# nrf52withamp.net
KiCad netlist of a schematic drawn in EAGLE
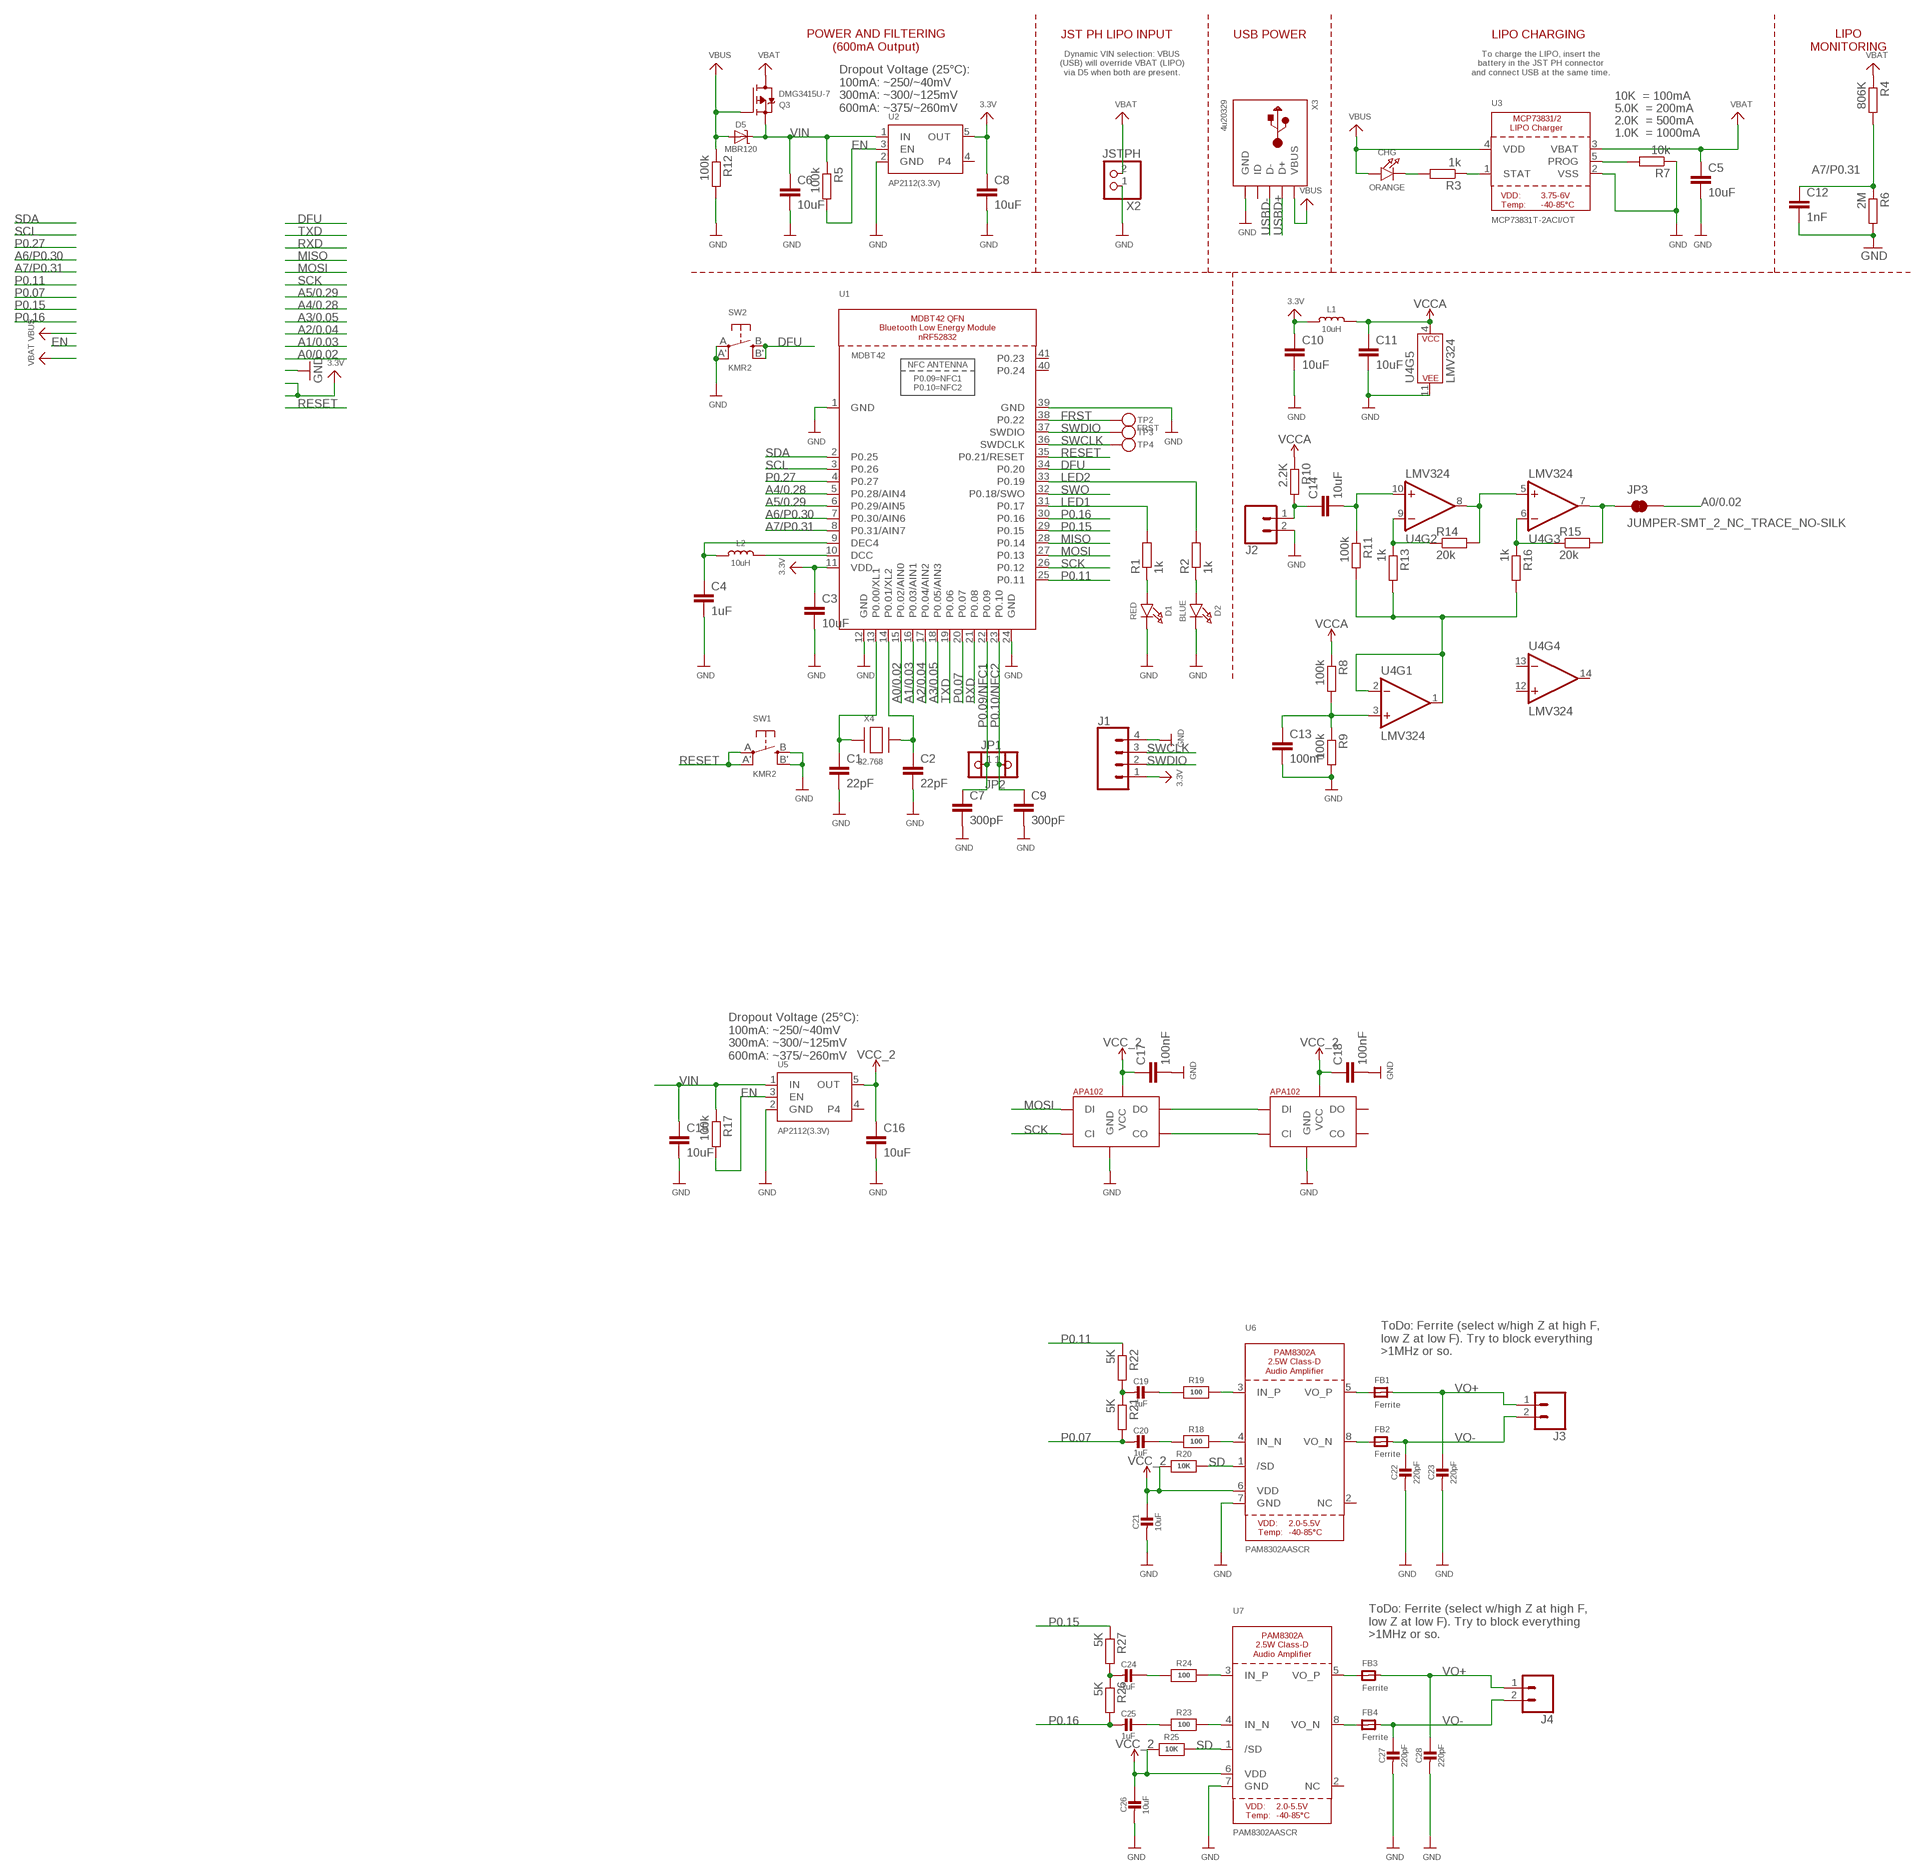
[diagram p0: schematic, sheet 1]

(export (version "E")
  (design (tool "Eeschema 10.0.6"))
  (components
    (comp (ref "C1")
      (value "22pF")
      (footprint "eagle-import:C0805")
      (libsource (lib "eagle-import") (part "C-EUC0805"))
    )
    (comp (ref "C2")
      (value "22pF")
      (footprint "eagle-import:C0805")
      (libsource (lib "eagle-import") (part "C-EUC0805"))
    )
    (comp (ref "C3")
      (value "10uF")
      (footprint "eagle-import:C0805")
      (libsource (lib "eagle-import") (part "C-EUC0805"))
    )
    (comp (ref "C4")
      (value "1uF")
      (footprint "eagle-import:C0805")
      (libsource (lib "eagle-import") (part "C-EUC0805"))
    )
    (comp (ref "C5")
      (value "10uF")
      (footprint "eagle-import:C0805")
      (libsource (lib "eagle-import") (part "C-EUC0805"))
    )
    (comp (ref "C6")
      (value "10uF")
      (footprint "eagle-import:C0805")
      (libsource (lib "eagle-import") (part "C-EUC0805"))
    )
    (comp (ref "C7")
      (value "300pF")
      (footprint "eagle-import:C0805")
      (libsource (lib "eagle-import") (part "C-EUC0805"))
    )
    (comp (ref "C8")
      (value "10uF")
      (footprint "eagle-import:C0805")
      (libsource (lib "eagle-import") (part "C-EUC0805"))
    )
    (comp (ref "C9")
      (value "300pF")
      (footprint "eagle-import:C0805")
      (libsource (lib "eagle-import") (part "C-EUC0805"))
    )
    (comp (ref "C10")
      (value "10uF")
      (footprint "eagle-import:C0805")
      (libsource (lib "eagle-import") (part "C-EUC0805"))
    )
    (comp (ref "C11")
      (value "10uF")
      (footprint "eagle-import:C0805")
      (libsource (lib "eagle-import") (part "C-EUC0805"))
    )
    (comp (ref "C12")
      (value "1nF")
      (footprint "eagle-import:C0805")
      (libsource (lib "eagle-import") (part "C-EUC0805"))
    )
    (comp (ref "C13")
      (value "100nF")
      (footprint "eagle-import:C0805")
      (libsource (lib "eagle-import") (part "C-EUC0805"))
    )
    (comp (ref "C14")
      (value "10uF")
      (footprint "eagle-import:C0805")
      (libsource (lib "eagle-import") (part "C-EUC0805"))
    )
    (comp (ref "C15")
      (value "10uF")
      (footprint "eagle-import:C0805")
      (libsource (lib "eagle-import") (part "C-EUC0805"))
    )
    (comp (ref "C16")
      (value "10uF")
      (footprint "eagle-import:C0805")
      (libsource (lib "eagle-import") (part "C-EUC0805"))
    )
    (comp (ref "C17")
      (value "100nF")
      (footprint "eagle-import:C0805")
      (libsource (lib "eagle-import") (part "C-EUC0805"))
    )
    (comp (ref "C18")
      (value "100nF")
      (footprint "eagle-import:C0805")
      (libsource (lib "eagle-import") (part "C-EUC0805"))
    )
    (comp (ref "C19")
      (value "1uF")
      (footprint "eagle-import:0805-NO")
      (libsource (lib "eagle-import") (part "CAP_CERAMIC0805-NOOUTLINE"))
    )
    (comp (ref "C20")
      (value "1uF")
      (footprint "eagle-import:0805-NO")
      (libsource (lib "eagle-import") (part "CAP_CERAMIC0805-NOOUTLINE"))
    )
    (comp (ref "C21")
      (value "10uF")
      (footprint "eagle-import:0805-NO")
      (libsource (lib "eagle-import") (part "CAP_CERAMIC0805-NOOUTLINE"))
    )
    (comp (ref "C22")
      (value "220pF")
      (footprint "eagle-import:0805-NO")
      (libsource (lib "eagle-import") (part "CAP_CERAMIC0805-NOOUTLINE"))
    )
    (comp (ref "C23")
      (value "220pF")
      (footprint "eagle-import:0805-NO")
      (libsource (lib "eagle-import") (part "CAP_CERAMIC0805-NOOUTLINE"))
    )
    (comp (ref "C24")
      (value "1uF")
      (footprint "eagle-import:0805-NO")
      (libsource (lib "eagle-import") (part "CAP_CERAMIC0805-NOOUTLINE"))
    )
    (comp (ref "C25")
      (value "1uF")
      (footprint "eagle-import:0805-NO")
      (libsource (lib "eagle-import") (part "CAP_CERAMIC0805-NOOUTLINE"))
    )
    (comp (ref "C26")
      (value "10uF")
      (footprint "eagle-import:0805-NO")
      (libsource (lib "eagle-import") (part "CAP_CERAMIC0805-NOOUTLINE"))
    )
    (comp (ref "C27")
      (value "220pF")
      (footprint "eagle-import:0805-NO")
      (libsource (lib "eagle-import") (part "CAP_CERAMIC0805-NOOUTLINE"))
    )
    (comp (ref "C28")
      (value "220pF")
      (footprint "eagle-import:0805-NO")
      (libsource (lib "eagle-import") (part "CAP_CERAMIC0805-NOOUTLINE"))
    )
    (comp (ref "CHG")
      (value "ORANGE")
      (footprint "eagle-import:CHIPLED_0805_NOOUTLINE")
      (libsource (lib "eagle-import") (part "LED0805_NOOUTLINE"))
    )
    (comp (ref "D1")
      (value "RED")
      (footprint "eagle-import:CHIPLED_0805_NOOUTLINE")
      (libsource (lib "eagle-import") (part "LED0805_NOOUTLINE"))
    )
    (comp (ref "D2")
      (value "BLUE")
      (footprint "eagle-import:CHIPLED_0805_NOOUTLINE")
      (libsource (lib "eagle-import") (part "LED0805_NOOUTLINE"))
    )
    (comp (ref "D5")
      (value "MBR120")
      (footprint "eagle-import:SOD-123")
      (libsource (lib "eagle-import") (part "DIODE-SCHOTTKYSOD-123"))
    )
    (comp (ref "FB1")
      (value "Ferrite")
      (footprint "eagle-import:_0805")
      (libsource (lib "eagle-import") (part "FERRITE_0805"))
    )
    (comp (ref "FB2")
      (value "Ferrite")
      (footprint "eagle-import:_0805")
      (libsource (lib "eagle-import") (part "FERRITE_0805"))
    )
    (comp (ref "FB3")
      (value "Ferrite")
      (footprint "eagle-import:_0805")
      (libsource (lib "eagle-import") (part "FERRITE_0805"))
    )
    (comp (ref "FB4")
      (value "Ferrite")
      (footprint "eagle-import:_0805")
      (libsource (lib "eagle-import") (part "FERRITE_0805"))
    )
    (comp (ref "J1")
      (value "CONN_04SMD")
      (footprint "eagle-import:1X04_SMD_RA_MALE")
      (libsource (lib "eagle-import") (part "CONN_04SMD"))
    )
    (comp (ref "J2")
      (value "CONN_02")
      (footprint "eagle-import:1X02")
      (libsource (lib "eagle-import") (part "CONN_02"))
    )
    (comp (ref "J3")
      (value "CONN_02")
      (footprint "eagle-import:1X02")
      (libsource (lib "eagle-import") (part "CONN_02"))
    )
    (comp (ref "J4")
      (value "CONN_02")
      (footprint "eagle-import:1X02")
      (libsource (lib "eagle-import") (part "CONN_02"))
    )
    (comp (ref "JP1")
      (value "HEADER-1X12MM")
      (footprint "eagle-import:1X01_2MM")
      (libsource (lib "eagle-import") (part "HEADER-1X12MM"))
    )
    (comp (ref "JP2")
      (value "HEADER-1X12MM")
      (footprint "eagle-import:1X01_2MM")
      (libsource (lib "eagle-import") (part "HEADER-1X12MM"))
    )
    (comp (ref "JP3")
      (value "JUMPER-SMT_2_NC_TRACE_NO-SILK")
      (footprint "eagle-import:SMT-JUMPER_2_NC_TRACE_NO-SILK")
      (libsource (lib "eagle-import") (part "JUMPER-SMT_2_NC_TRACE_NO-SILK"))
    )
    (comp (ref "L1")
      (value "10uH")
      (footprint "eagle-import:0805-NO@1")
      (libsource (lib "eagle-import") (part "INDUCTOR0805-NO"))
    )
    (comp (ref "L2")
      (value "10uH")
      (footprint "eagle-import:0805-NO@1")
      (libsource (lib "eagle-import") (part "INDUCTOR0805-NO"))
    )
    (comp (ref "Q3")
      (value "DMG3415U-7")
      (footprint "eagle-import:SOT23-R")
      (libsource (lib "eagle-import") (part "MOSFET-P"))
    )
    (comp (ref "R1")
      (value "1k")
      (footprint "eagle-import:R0805")
      (libsource (lib "eagle-import") (part "R-EU_R0805"))
    )
    (comp (ref "R2")
      (value "1k")
      (footprint "eagle-import:R0805")
      (libsource (lib "eagle-import") (part "R-EU_R0805"))
    )
    (comp (ref "R3")
      (value "1k")
      (footprint "eagle-import:R0805")
      (libsource (lib "eagle-import") (part "R-EU_R0805"))
    )
    (comp (ref "R4")
      (value "806K")
      (footprint "eagle-import:R0805")
      (libsource (lib "eagle-import") (part "R-EU_R0805"))
    )
    (comp (ref "R5")
      (value "100k")
      (footprint "eagle-import:R0805")
      (libsource (lib "eagle-import") (part "R-EU_R0805"))
    )
    (comp (ref "R6")
      (value "2M")
      (footprint "eagle-import:R0805")
      (libsource (lib "eagle-import") (part "R-EU_R0805"))
    )
    (comp (ref "R7")
      (value "10k")
      (footprint "eagle-import:R0805")
      (libsource (lib "eagle-import") (part "R-EU_R0805"))
    )
    (comp (ref "R8")
      (value "100k")
      (footprint "eagle-import:R0805")
      (libsource (lib "eagle-import") (part "R-EU_R0805"))
    )
    (comp (ref "R9")
      (value "100k")
      (footprint "eagle-import:R0805")
      (libsource (lib "eagle-import") (part "R-EU_R0805"))
    )
    (comp (ref "R10")
      (value "2.2K")
      (footprint "eagle-import:R0805")
      (libsource (lib "eagle-import") (part "R-EU_R0805"))
    )
    (comp (ref "R11")
      (value "100k")
      (footprint "eagle-import:R0805")
      (libsource (lib "eagle-import") (part "R-EU_R0805"))
    )
    (comp (ref "R12")
      (value "100k")
      (footprint "eagle-import:R0805")
      (libsource (lib "eagle-import") (part "R-EU_R0805"))
    )
    (comp (ref "R13")
      (value "1k")
      (footprint "eagle-import:R0805")
      (libsource (lib "eagle-import") (part "R-EU_R0805"))
    )
    (comp (ref "R14")
      (value "20k")
      (footprint "eagle-import:R0805")
      (libsource (lib "eagle-import") (part "R-EU_R0805"))
    )
    (comp (ref "R15")
      (value "20k")
      (footprint "eagle-import:R0805")
      (libsource (lib "eagle-import") (part "R-EU_R0805"))
    )
    (comp (ref "R16")
      (value "1k")
      (footprint "eagle-import:R0805")
      (libsource (lib "eagle-import") (part "R-EU_R0805"))
    )
    (comp (ref "R17")
      (value "100k")
      (footprint "eagle-import:R0805")
      (libsource (lib "eagle-import") (part "R-EU_R0805"))
    )
    (comp (ref "R18")
      (value "100")
      (footprint "eagle-import:0805-NO")
      (libsource (lib "eagle-import") (part "RESISTOR0805_NOOUTLINE"))
    )
    (comp (ref "R19")
      (value "100")
      (footprint "eagle-import:0805-NO")
      (libsource (lib "eagle-import") (part "RESISTOR0805_NOOUTLINE"))
    )
    (comp (ref "R20")
      (value "10K")
      (footprint "eagle-import:0805-NO")
      (libsource (lib "eagle-import") (part "RESISTOR0805_NOOUTLINE"))
    )
    (comp (ref "R21")
      (value "5K")
      (footprint "eagle-import:R0805")
      (libsource (lib "eagle-import") (part "R-EU_R0805"))
    )
    (comp (ref "R22")
      (value "5K")
      (footprint "eagle-import:R0805")
      (libsource (lib "eagle-import") (part "R-EU_R0805"))
    )
    (comp (ref "R23")
      (value "100")
      (footprint "eagle-import:0805-NO")
      (libsource (lib "eagle-import") (part "RESISTOR0805_NOOUTLINE"))
    )
    (comp (ref "R24")
      (value "100")
      (footprint "eagle-import:0805-NO")
      (libsource (lib "eagle-import") (part "RESISTOR0805_NOOUTLINE"))
    )
    (comp (ref "R25")
      (value "10K")
      (footprint "eagle-import:0805-NO")
      (libsource (lib "eagle-import") (part "RESISTOR0805_NOOUTLINE"))
    )
    (comp (ref "R26")
      (value "5K")
      (footprint "eagle-import:R0805")
      (libsource (lib "eagle-import") (part "R-EU_R0805"))
    )
    (comp (ref "R27")
      (value "5K")
      (footprint "eagle-import:R0805")
      (libsource (lib "eagle-import") (part "R-EU_R0805"))
    )
    (comp (ref "SW1")
      (value "KMR2")
      (footprint "eagle-import:BTN_KMR2_4.6X2.8")
      (libsource (lib "eagle-import") (part "SWITCH_TACT_SMT4.6X2.8"))
    )
    (comp (ref "SW2")
      (value "KMR2")
      (footprint "eagle-import:BTN_KMR2_4.6X2.8")
      (libsource (lib "eagle-import") (part "SWITCH_TACT_SMT4.6X2.8"))
    )
    (comp (ref "TP2")
      (value "FRST")
      (footprint "eagle-import:PAD-1.5X2.0")
      (libsource (lib "eagle-import") (part "TESTPOINT1.5X2.0MM_NOCREAM"))
    )
    (comp (ref "TP3")
      (value "TESTPOINTROUND2MM")
      (footprint "eagle-import:TESTPOINT_ROUND_2MM")
      (libsource (lib "eagle-import") (part "TESTPOINTROUND2MM"))
    )
    (comp (ref "TP4")
      (value "TESTPOINTROUND2MM")
      (footprint "eagle-import:TESTPOINT_ROUND_2MM")
      (libsource (lib "eagle-import") (part "TESTPOINTROUND2MM"))
    )
    (comp (ref "U$45")
      (value "APA1022020")
      (footprint "eagle-import:APA102_2020")
      (libsource (lib "eagle-import") (part "APA1022020"))
    )
    (comp (ref "U$51")
      (value "APA1022020")
      (footprint "eagle-import:APA102_2020")
      (libsource (lib "eagle-import") (part "APA1022020"))
    )
    (comp (ref "U1")
      (value "MDBT42")
      (footprint "eagle-import:BLE_MODULE_RAYTAC_MDBT42")
      (libsource (lib "eagle-import") (part "NRF52832_MODULE_MDBT42"))
    )
    (comp (ref "U2")
      (value "AP2112(3.3V)")
      (footprint "eagle-import:SOT23-5")
      (libsource (lib "eagle-import") (part "VREG_SOT23-5"))
    )
    (comp (ref "U3")
      (value "MCP73831T-2ACI/OT")
      (footprint "eagle-import:SOT23-5")
      (libsource (lib "eagle-import") (part "MCP73831/2"))
    )
    (comp (ref "U4")
      (value "LMV324")
      (footprint "eagle-import:SO14")
      (libsource (lib "eagle-import") (part "LMV324"))
    )
    (comp (ref "U5")
      (value "AP2112(3.3V)")
      (footprint "eagle-import:SOT23-5")
      (libsource (lib "eagle-import") (part "VREG_SOT23-5"))
    )
    (comp (ref "U6")
      (value "PAM8302AASCR")
      (footprint "eagle-import:MSOP8_0.65MM")
      (libsource (lib "eagle-import") (part "AUDIOAMP_PAM8302A"))
    )
    (comp (ref "U7")
      (value "PAM8302AASCR")
      (footprint "eagle-import:MSOP8_0.65MM")
      (libsource (lib "eagle-import") (part "AUDIOAMP_PAM8302A"))
    )
    (comp (ref "X2")
      (value "JSTPH")
      (footprint "eagle-import:JSTPH2")
      (libsource (lib "eagle-import") (part "CON_JST_PH_2PIN"))
    )
    (comp (ref "X3")
      (value "4u20329")
      (footprint "eagle-import:4UCONN_20329_V2")
      (libsource (lib "eagle-import") (part "USB_MICRO_20329_V2"))
    )
    (comp (ref "X4")
      (value "32.768")
      (footprint "eagle-import:XTAL3215")
      (libsource (lib "eagle-import") (part "XTAL-3.2X1.5"))
    )
  )
  (nets
    (net (code "1") (name "/A0{slash}0.02") (class "Default")
      (node (ref "JP3") (pin "2") (pinfunction "2_2") (pintype "passive"))
      (node (ref "U1") (pin "15") (pinfunction "P0.02/AIN0_15") (pintype "bidirectional"))
    )
    (net (code "2") (name "/A1{slash}0.03") (class "Default")
      (node (ref "U1") (pin "16") (pinfunction "P0.03/AIN1_16") (pintype "bidirectional"))
    )
    (net (code "3") (name "/A2{slash}0.04") (class "Default")
      (node (ref "U1") (pin "17") (pinfunction "P0.04/AIN2_17") (pintype "bidirectional"))
    )
    (net (code "4") (name "/A3{slash}0.05") (class "Default")
      (node (ref "U1") (pin "18") (pinfunction "P0.05/AIN3_18") (pintype "bidirectional"))
    )
    (net (code "5") (name "/A4{slash}0.28") (class "Default")
      (node (ref "U1") (pin "5") (pinfunction "P0.28/AIN4_5") (pintype "bidirectional"))
    )
    (net (code "6") (name "/A5{slash}0.29") (class "Default")
      (node (ref "U1") (pin "6") (pinfunction "P0.29/AIN5_6") (pintype "bidirectional"))
    )
    (net (code "7") (name "/A6{slash}P0.30") (class "Default")
      (node (ref "U1") (pin "7") (pinfunction "P0.30/AIN6_7") (pintype "bidirectional"))
    )
    (net (code "8") (name "/A7{slash}P0.31") (class "Default")
      (node (ref "C12") (pin "1") (pinfunction "1_1") (pintype "passive"))
      (node (ref "R4") (pin "2") (pinfunction "2_2") (pintype "passive"))
      (node (ref "R6") (pin "1") (pinfunction "1_1") (pintype "passive"))
      (node (ref "U1") (pin "8") (pinfunction "P0.31/AIN7_8") (pintype "bidirectional"))
    )
    (net (code "9") (name "/DFU") (class "Default")
      (node (ref "SW2") (pin "B") (pinfunction "S_B") (pintype "passive"))
      (node (ref "SW2") (pin "B'") (pinfunction "S1_B'") (pintype "passive"))
      (node (ref "U1") (pin "34") (pinfunction "P0.20_34") (pintype "bidirectional"))
    )
    (net (code "10") (name "/EN") (class "Default")
      (node (ref "R17") (pin "2") (pinfunction "2_2") (pintype "passive"))
      (node (ref "R5") (pin "2") (pinfunction "2_2") (pintype "passive"))
      (node (ref "U2") (pin "3") (pinfunction "EN_3") (pintype "input"))
      (node (ref "U5") (pin "3") (pinfunction "EN_3") (pintype "input"))
    )
    (net (code "11") (name "/FRST") (class "Default")
      (node (ref "TP2") (pin "P$1") (pinfunction "P$1_P$1") (pintype "bidirectional"))
      (node (ref "U1") (pin "38") (pinfunction "P0.22_38") (pintype "bidirectional"))
    )
    (net (code "12") (name "/LED1") (class "Default")
      (node (ref "R1") (pin "2") (pinfunction "2_2") (pintype "passive"))
      (node (ref "U1") (pin "31") (pinfunction "P0.17_31") (pintype "bidirectional"))
    )
    (net (code "13") (name "/LED2") (class "Default")
      (node (ref "R2") (pin "2") (pinfunction "2_2") (pintype "passive"))
      (node (ref "U1") (pin "33") (pinfunction "P0.19_33") (pintype "bidirectional"))
    )
    (net (code "14") (name "/MISO") (class "Default")
      (node (ref "U1") (pin "28") (pinfunction "P0.14_28") (pintype "bidirectional"))
    )
    (net (code "15") (name "/MOSI") (class "Default")
      (node (ref "U$45") (pin "D_IN") (pinfunction "DI_D_IN") (pintype "bidirectional"))
      (node (ref "U1") (pin "27") (pinfunction "P0.13_27") (pintype "bidirectional"))
    )
    (net (code "16") (name "/P0.07") (class "Default")
      (node (ref "C20") (pin "2") (pinfunction "2_2") (pintype "passive"))
      (node (ref "R21") (pin "2") (pinfunction "2_2") (pintype "passive"))
      (node (ref "U1") (pin "20") (pinfunction "P0.07_20") (pintype "bidirectional"))
    )
    (net (code "17") (name "/P0.09{slash}NFC1") (class "Default")
      (node (ref "C7") (pin "1") (pinfunction "1_1") (pintype "passive"))
      (node (ref "JP2") (pin "1") (pinfunction "1_1") (pintype "passive"))
      (node (ref "U1") (pin "22") (pinfunction "P0.09_22") (pintype "bidirectional"))
    )
    (net (code "18") (name "/P0.10{slash}NFC2") (class "Default")
      (node (ref "C9") (pin "1") (pinfunction "1_1") (pintype "passive"))
      (node (ref "JP1") (pin "1") (pinfunction "1_1") (pintype "passive"))
      (node (ref "U1") (pin "23") (pinfunction "P0.10_23") (pintype "bidirectional"))
    )
    (net (code "19") (name "/P0.11") (class "Default")
      (node (ref "R22") (pin "1") (pinfunction "1_1") (pintype "passive"))
      (node (ref "U1") (pin "25") (pinfunction "P0.11_25") (pintype "bidirectional"))
    )
    (net (code "20") (name "/P0.15") (class "Default")
      (node (ref "R27") (pin "1") (pinfunction "1_1") (pintype "passive"))
      (node (ref "U1") (pin "29") (pinfunction "P0.15_29") (pintype "bidirectional"))
    )
    (net (code "21") (name "/P0.16") (class "Default")
      (node (ref "C25") (pin "2") (pinfunction "2_2") (pintype "passive"))
      (node (ref "R26") (pin "2") (pinfunction "2_2") (pintype "passive"))
      (node (ref "U1") (pin "30") (pinfunction "P0.16_30") (pintype "bidirectional"))
    )
    (net (code "22") (name "/P0.27") (class "Default")
      (node (ref "U1") (pin "4") (pinfunction "P0.27_4") (pintype "bidirectional"))
    )
    (net (code "23") (name "/RESET") (class "Default")
      (node (ref "SW1") (pin "A") (pinfunction "P_A") (pintype "passive"))
      (node (ref "SW1") (pin "A'") (pinfunction "P1_A'") (pintype "passive"))
      (node (ref "U1") (pin "35") (pinfunction "P0.21/RESET_35") (pintype "bidirectional"))
    )
    (net (code "24") (name "/RXD") (class "Default")
      (node (ref "U1") (pin "21") (pinfunction "P0.08_21") (pintype "bidirectional"))
    )
    (net (code "25") (name "/SCK") (class "Default")
      (node (ref "U$45") (pin "C_IN") (pinfunction "CI_C_IN") (pintype "bidirectional"))
      (node (ref "U1") (pin "26") (pinfunction "P0.12_26") (pintype "bidirectional"))
    )
    (net (code "26") (name "/SCL") (class "Default")
      (node (ref "U1") (pin "3") (pinfunction "P0.26_3") (pintype "bidirectional"))
    )
    (net (code "27") (name "/SD") (class "Default")
      (node (ref "R20") (pin "2") (pinfunction "2_2") (pintype "passive"))
      (node (ref "R25") (pin "2") (pinfunction "2_2") (pintype "passive"))
      (node (ref "U6") (pin "1") (pinfunction "/SD_1") (pintype "input"))
      (node (ref "U7") (pin "1") (pinfunction "/SD_1") (pintype "input"))
    )
    (net (code "28") (name "/SDA") (class "Default")
      (node (ref "U1") (pin "2") (pinfunction "P0.25_2") (pintype "bidirectional"))
    )
    (net (code "29") (name "/SWCLK") (class "Default")
      (node (ref "J1") (pin "3") (pinfunction "3_3") (pintype "passive"))
      (node (ref "TP4") (pin "P$1") (pinfunction "P$1_P$1") (pintype "bidirectional"))
      (node (ref "U1") (pin "36") (pinfunction "SWDCLK_36") (pintype "bidirectional"))
    )
    (net (code "30") (name "/SWDIO") (class "Default")
      (node (ref "J1") (pin "2") (pinfunction "2_2") (pintype "passive"))
      (node (ref "TP3") (pin "P$1") (pinfunction "P$1_P$1") (pintype "bidirectional"))
      (node (ref "U1") (pin "37") (pinfunction "SWDIO_37") (pintype "bidirectional"))
    )
    (net (code "31") (name "/SWO") (class "Default")
      (node (ref "U1") (pin "32") (pinfunction "P0.18/SWO_32") (pintype "bidirectional"))
    )
    (net (code "32") (name "/TXD") (class "Default")
      (node (ref "U1") (pin "19") (pinfunction "P0.06_19") (pintype "bidirectional"))
    )
    (net (code "33") (name "/USBD+") (class "Default")
      (node (ref "X3") (pin "D+") (pinfunction "D+_D+") (pintype "bidirectional"))
    )
    (net (code "34") (name "/USBD-") (class "Default")
      (node (ref "X3") (pin "D-") (pinfunction "D-_D-") (pintype "bidirectional"))
    )
    (net (code "35") (name "/VIN") (class "Default")
      (node (ref "C15") (pin "1") (pinfunction "1_1") (pintype "passive"))
      (node (ref "C6") (pin "1") (pinfunction "1_1") (pintype "passive"))
      (node (ref "D5") (pin "C") (pinfunction "C_C") (pintype "passive"))
      (node (ref "Q3") (pin "2") (pinfunction "S_2") (pintype "passive"))
      (node (ref "R17") (pin "1") (pinfunction "1_1") (pintype "passive"))
      (node (ref "R5") (pin "1") (pinfunction "1_1") (pintype "passive"))
      (node (ref "U2") (pin "1") (pinfunction "IN_1") (pintype "power_in"))
      (node (ref "U5") (pin "1") (pinfunction "IN_1") (pintype "power_in"))
    )
    (net (code "36") (name "/VO+") (class "Default")
      (node (ref "C23") (pin "1") (pinfunction "1_1") (pintype "passive"))
      (node (ref "C28") (pin "1") (pinfunction "1_1") (pintype "passive"))
      (node (ref "FB1") (pin "2") (pinfunction "P$2_2") (pintype "passive"))
      (node (ref "FB3") (pin "2") (pinfunction "P$2_2") (pintype "passive"))
      (node (ref "J3") (pin "1") (pinfunction "1_1") (pintype "passive"))
      (node (ref "J4") (pin "1") (pinfunction "1_1") (pintype "passive"))
    )
    (net (code "37") (name "/VO-") (class "Default")
      (node (ref "C22") (pin "1") (pinfunction "1_1") (pintype "passive"))
      (node (ref "C27") (pin "1") (pinfunction "1_1") (pintype "passive"))
      (node (ref "FB2") (pin "2") (pinfunction "P$2_2") (pintype "passive"))
      (node (ref "FB4") (pin "2") (pinfunction "P$2_2") (pintype "passive"))
      (node (ref "J3") (pin "2") (pinfunction "2_2") (pintype "passive"))
      (node (ref "J4") (pin "2") (pinfunction "2_2") (pintype "passive"))
    )
    (net (code "38") (name "3.3V") (class "Default")
      (node (ref "C10") (pin "1") (pinfunction "1_1") (pintype "passive"))
      (node (ref "C3") (pin "1") (pinfunction "1_1") (pintype "passive"))
      (node (ref "C8") (pin "1") (pinfunction "1_1") (pintype "passive"))
      (node (ref "J1") (pin "1") (pinfunction "1_1") (pintype "passive"))
      (node (ref "L1") (pin "1") (pinfunction "1_1") (pintype "passive"))
      (node (ref "U1") (pin "11") (pinfunction "VDD_11") (pintype "bidirectional"))
      (node (ref "U2") (pin "5") (pinfunction "OUT_5") (pintype "power_in"))
    )
    (net (code "39") (name "GND") (class "Default")
      (node (ref "C1") (pin "2") (pinfunction "2_2") (pintype "passive"))
      (node (ref "C10") (pin "2") (pinfunction "2_2") (pintype "passive"))
      (node (ref "C11") (pin "2") (pinfunction "2_2") (pintype "passive"))
      (node (ref "C12") (pin "2") (pinfunction "2_2") (pintype "passive"))
      (node (ref "C13") (pin "2") (pinfunction "2_2") (pintype "passive"))
      (node (ref "C15") (pin "2") (pinfunction "2_2") (pintype "passive"))
      (node (ref "C16") (pin "2") (pinfunction "2_2") (pintype "passive"))
      (node (ref "C17") (pin "2") (pinfunction "2_2") (pintype "passive"))
      (node (ref "C18") (pin "2") (pinfunction "2_2") (pintype "passive"))
      (node (ref "C2") (pin "2") (pinfunction "2_2") (pintype "passive"))
      (node (ref "C21") (pin "2") (pinfunction "2_2") (pintype "passive"))
      (node (ref "C22") (pin "2") (pinfunction "2_2") (pintype "passive"))
      (node (ref "C23") (pin "2") (pinfunction "2_2") (pintype "passive"))
      (node (ref "C26") (pin "2") (pinfunction "2_2") (pintype "passive"))
      (node (ref "C27") (pin "2") (pinfunction "2_2") (pintype "passive"))
      (node (ref "C28") (pin "2") (pinfunction "2_2") (pintype "passive"))
      (node (ref "C3") (pin "2") (pinfunction "2_2") (pintype "passive"))
      (node (ref "C4") (pin "2") (pinfunction "2_2") (pintype "passive"))
      (node (ref "C5") (pin "2") (pinfunction "2_2") (pintype "passive"))
      (node (ref "C6") (pin "2") (pinfunction "2_2") (pintype "passive"))
      (node (ref "C7") (pin "2") (pinfunction "2_2") (pintype "passive"))
      (node (ref "C8") (pin "2") (pinfunction "2_2") (pintype "passive"))
      (node (ref "C9") (pin "2") (pinfunction "2_2") (pintype "passive"))
      (node (ref "D1") (pin "C") (pinfunction "C_C") (pintype "passive"))
      (node (ref "D2") (pin "C") (pinfunction "C_C") (pintype "passive"))
      (node (ref "J1") (pin "4") (pinfunction "4_4") (pintype "passive"))
      (node (ref "J2") (pin "2") (pinfunction "2_2") (pintype "passive"))
      (node (ref "R12") (pin "2") (pinfunction "2_2") (pintype "passive"))
      (node (ref "R6") (pin "2") (pinfunction "2_2") (pintype "passive"))
      (node (ref "R7") (pin "1") (pinfunction "1_1") (pintype "passive"))
      (node (ref "R9") (pin "2") (pinfunction "2_2") (pintype "passive"))
      (node (ref "SW1") (pin "B") (pinfunction "S_B") (pintype "passive"))
      (node (ref "SW1") (pin "B'") (pinfunction "S1_B'") (pintype "passive"))
      (node (ref "SW2") (pin "A") (pinfunction "P_A") (pintype "passive"))
      (node (ref "SW2") (pin "A'") (pinfunction "P1_A'") (pintype "passive"))
      (node (ref "U$45") (pin "GND") (pinfunction "GND_GND") (pintype "bidirectional"))
      (node (ref "U$51") (pin "GND") (pinfunction "GND_GND") (pintype "bidirectional"))
      (node (ref "U1") (pin "1") (pinfunction "GND_1") (pintype "bidirectional"))
      (node (ref "U1") (pin "12") (pinfunction "GND_12") (pintype "bidirectional"))
      (node (ref "U1") (pin "24") (pinfunction "GND_24") (pintype "bidirectional"))
      (node (ref "U1") (pin "39") (pinfunction "GND_39") (pintype "bidirectional"))
      (node (ref "U2") (pin "2") (pinfunction "GND_2") (pintype "power_in"))
      (node (ref "U3") (pin "2") (pinfunction "VSS_2") (pintype "power_in"))
      (node (ref "U4") (pin "11") (pinfunction "P$V-_11") (pintype "bidirectional"))
      (node (ref "U5") (pin "2") (pinfunction "GND_2") (pintype "power_in"))
      (node (ref "U6") (pin "7") (pinfunction "GND_7") (pintype "power_in"))
      (node (ref "U7") (pin "7") (pinfunction "GND_7") (pintype "power_in"))
      (node (ref "X2") (pin "1") (pinfunction "1_1") (pintype "passive"))
      (node (ref "X3") (pin "BASE@1") (pinfunction "GND_BASE@1") (pintype "power_in"))
      (node (ref "X3") (pin "BASE@2") (pinfunction "GND_BASE@2") (pintype "power_in"))
      (node (ref "X3") (pin "GND") (pinfunction "GND_GND") (pintype "power_in"))
      (node (ref "X3") (pin "SPRT@1") (pinfunction "GND_SPRT@1") (pintype "power_in"))
      (node (ref "X3") (pin "SPRT@2") (pinfunction "GND_SPRT@2") (pintype "power_in"))
      (node (ref "X3") (pin "SPRT@3") (pinfunction "GND_SPRT@3") (pintype "power_in"))
      (node (ref "X3") (pin "SPRT@4") (pinfunction "GND_SPRT@4") (pintype "power_in"))
    )
    (net (code "40") (name "Net-(C14-Pad1)") (class "Default")
      (node (ref "C14") (pin "1") (pinfunction "1_1") (pintype "passive"))
      (node (ref "J2") (pin "1") (pinfunction "1_1") (pintype "passive"))
      (node (ref "R10") (pin "2") (pinfunction "2_2") (pintype "passive"))
    )
    (net (code "41") (name "Net-(C19-Pad1)") (class "Default")
      (node (ref "C19") (pin "1") (pinfunction "1_1") (pintype "passive"))
      (node (ref "R19") (pin "1") (pinfunction "1_1") (pintype "passive"))
    )
    (net (code "42") (name "Net-(C19-Pad2)") (class "Default")
      (node (ref "C19") (pin "2") (pinfunction "2_2") (pintype "passive"))
      (node (ref "R21") (pin "1") (pinfunction "1_1") (pintype "passive"))
      (node (ref "R22") (pin "2") (pinfunction "2_2") (pintype "passive"))
    )
    (net (code "43") (name "Net-(C20-Pad1)") (class "Default")
      (node (ref "C20") (pin "1") (pinfunction "1_1") (pintype "passive"))
      (node (ref "R18") (pin "1") (pinfunction "1_1") (pintype "passive"))
    )
    (net (code "44") (name "Net-(C24-Pad1)") (class "Default")
      (node (ref "C24") (pin "1") (pinfunction "1_1") (pintype "passive"))
      (node (ref "R24") (pin "1") (pinfunction "1_1") (pintype "passive"))
    )
    (net (code "45") (name "Net-(C24-Pad2)") (class "Default")
      (node (ref "C24") (pin "2") (pinfunction "2_2") (pintype "passive"))
      (node (ref "R26") (pin "1") (pinfunction "1_1") (pintype "passive"))
      (node (ref "R27") (pin "2") (pinfunction "2_2") (pintype "passive"))
    )
    (net (code "46") (name "Net-(C25-Pad1)") (class "Default")
      (node (ref "C25") (pin "1") (pinfunction "1_1") (pintype "passive"))
      (node (ref "R23") (pin "1") (pinfunction "1_1") (pintype "passive"))
    )
    (net (code "47") (name "Net-(CHG-PadC)") (class "Default")
      (node (ref "CHG") (pin "C") (pinfunction "C_C") (pintype "passive"))
      (node (ref "R3") (pin "2") (pinfunction "2_2") (pintype "passive"))
    )
    (net (code "48") (name "Net-(D1-PadA)") (class "Default")
      (node (ref "D1") (pin "A") (pinfunction "A_A") (pintype "passive"))
      (node (ref "R1") (pin "1") (pinfunction "1_1") (pintype "passive"))
    )
    (net (code "49") (name "Net-(D2-PadA)") (class "Default")
      (node (ref "D2") (pin "A") (pinfunction "A_A") (pintype "passive"))
      (node (ref "R2") (pin "1") (pinfunction "1_1") (pintype "passive"))
    )
    (net (code "50") (name "Net-(FB1-P$1)") (class "Default")
      (node (ref "FB1") (pin "1") (pinfunction "P$1_1") (pintype "passive"))
      (node (ref "U6") (pin "5") (pinfunction "VO_P_5") (pintype "output"))
    )
    (net (code "51") (name "Net-(FB2-P$1)") (class "Default")
      (node (ref "FB2") (pin "1") (pinfunction "P$1_1") (pintype "passive"))
      (node (ref "U6") (pin "8") (pinfunction "VO_N_8") (pintype "output"))
    )
    (net (code "52") (name "Net-(FB3-P$1)") (class "Default")
      (node (ref "FB3") (pin "1") (pinfunction "P$1_1") (pintype "passive"))
      (node (ref "U7") (pin "5") (pinfunction "VO_P_5") (pintype "output"))
    )
    (net (code "53") (name "Net-(FB4-P$1)") (class "Default")
      (node (ref "FB4") (pin "1") (pinfunction "P$1_1") (pintype "passive"))
      (node (ref "U7") (pin "8") (pinfunction "VO_N_8") (pintype "output"))
    )
    (net (code "54") (name "Net-(U$45-CO)") (class "Default")
      (node (ref "U$45") (pin "CL_OUT") (pinfunction "CO_CL_OUT") (pintype "bidirectional"))
      (node (ref "U$51") (pin "C_IN") (pinfunction "CI_C_IN") (pintype "bidirectional"))
    )
    (net (code "55") (name "Net-(U$45-DO)") (class "Default")
      (node (ref "U$45") (pin "D_OUT") (pinfunction "DO_D_OUT") (pintype "bidirectional"))
      (node (ref "U$51") (pin "D_IN") (pinfunction "DI_D_IN") (pintype "bidirectional"))
    )
    (net (code "56") (name "Net-(U1-DCC)") (class "Default")
      (node (ref "L2") (pin "2") (pinfunction "2_2") (pintype "passive"))
      (node (ref "U1") (pin "10") (pinfunction "DCC_10") (pintype "bidirectional"))
    )
    (net (code "57") (name "Net-(U1-DEC4)") (class "Default")
      (node (ref "C4") (pin "1") (pinfunction "1_1") (pintype "passive"))
      (node (ref "L2") (pin "1") (pinfunction "1_1") (pintype "passive"))
      (node (ref "U1") (pin "9") (pinfunction "DEC4_9") (pintype "bidirectional"))
    )
    (net (code "58") (name "Net-(U1-P0.00{slash}XL1)") (class "Default")
      (node (ref "C1") (pin "1") (pinfunction "1_1") (pintype "passive"))
      (node (ref "U1") (pin "13") (pinfunction "P0.00/XL1_13") (pintype "bidirectional"))
      (node (ref "X4") (pin "P$1") (pinfunction "P$1_P$1") (pintype "bidirectional"))
    )
    (net (code "59") (name "Net-(U1-P0.01{slash}XL2)") (class "Default")
      (node (ref "C2") (pin "1") (pinfunction "1_1") (pintype "passive"))
      (node (ref "U1") (pin "14") (pinfunction "P0.01/XL2_14") (pintype "bidirectional"))
      (node (ref "X4") (pin "P$2") (pinfunction "P$2_P$2") (pintype "bidirectional"))
    )
    (net (code "60") (name "Net-(U3-PROG)") (class "Default")
      (node (ref "R7") (pin "2") (pinfunction "2_2") (pintype "passive"))
      (node (ref "U3") (pin "5") (pinfunction "PROG_5") (pintype "input"))
    )
    (net (code "61") (name "Net-(U3-STAT)") (class "Default")
      (node (ref "R3") (pin "1") (pinfunction "1_1") (pintype "passive"))
      (node (ref "U3") (pin "1") (pinfunction "STAT_1") (pintype "output"))
    )
    (net (code "62") (name "Net-(U4A-+IN)") (class "Default")
      (node (ref "C13") (pin "1") (pinfunction "1_1") (pintype "passive"))
      (node (ref "R8") (pin "2") (pinfunction "2_2") (pintype "passive"))
      (node (ref "R9") (pin "1") (pinfunction "1_1") (pintype "passive"))
      (node (ref "U4") (pin "3") (pinfunction "+IN_3") (pintype "input"))
    )
    (net (code "63") (name "Net-(U4A--IN)") (class "Default")
      (node (ref "R11") (pin "2") (pinfunction "2_2") (pintype "passive"))
      (node (ref "R13") (pin "2") (pinfunction "2_2") (pintype "passive"))
      (node (ref "R16") (pin "2") (pinfunction "2_2") (pintype "passive"))
      (node (ref "U4") (pin "1") (pinfunction "OUT_1") (pintype "output"))
      (node (ref "U4") (pin "2") (pinfunction "-IN_2") (pintype "input"))
    )
    (net (code "64") (name "Net-(U4B-+IN)") (class "Default")
      (node (ref "C14") (pin "2") (pinfunction "2_2") (pintype "passive"))
      (node (ref "R11") (pin "1") (pinfunction "1_1") (pintype "passive"))
      (node (ref "U4") (pin "10") (pinfunction "+IN_10") (pintype "input"))
    )
    (net (code "65") (name "Net-(U4B--IN)") (class "Default")
      (node (ref "R13") (pin "1") (pinfunction "1_1") (pintype "passive"))
      (node (ref "R14") (pin "1") (pinfunction "1_1") (pintype "passive"))
      (node (ref "U4") (pin "9") (pinfunction "-IN_9") (pintype "input"))
    )
    (net (code "66") (name "Net-(U4B-OUT)") (class "Default")
      (node (ref "R14") (pin "2") (pinfunction "2_2") (pintype "passive"))
      (node (ref "U4") (pin "5") (pinfunction "+IN_5") (pintype "input"))
      (node (ref "U4") (pin "8") (pinfunction "OUT_8") (pintype "output"))
    )
    (net (code "67") (name "Net-(U4C--IN)") (class "Default")
      (node (ref "R15") (pin "1") (pinfunction "1_1") (pintype "passive"))
      (node (ref "R16") (pin "1") (pinfunction "1_1") (pintype "passive"))
      (node (ref "U4") (pin "6") (pinfunction "-IN_6") (pintype "input"))
    )
    (net (code "68") (name "Net-(U4C-OUT)") (class "Default")
      (node (ref "JP3") (pin "1") (pinfunction "1_1") (pintype "passive"))
      (node (ref "R15") (pin "2") (pinfunction "2_2") (pintype "passive"))
      (node (ref "U4") (pin "7") (pinfunction "OUT_7") (pintype "output"))
    )
    (net (code "69") (name "Net-(U6-IN_N)") (class "Default")
      (node (ref "R18") (pin "2") (pinfunction "2_2") (pintype "passive"))
      (node (ref "U6") (pin "4") (pinfunction "IN_N_4") (pintype "input"))
    )
    (net (code "70") (name "Net-(U6-IN_P)") (class "Default")
      (node (ref "R19") (pin "2") (pinfunction "2_2") (pintype "passive"))
      (node (ref "U6") (pin "3") (pinfunction "IN_P_3") (pintype "input"))
    )
    (net (code "71") (name "Net-(U7-IN_N)") (class "Default")
      (node (ref "R23") (pin "2") (pinfunction "2_2") (pintype "passive"))
      (node (ref "U7") (pin "4") (pinfunction "IN_N_4") (pintype "input"))
    )
    (net (code "72") (name "Net-(U7-IN_P)") (class "Default")
      (node (ref "R24") (pin "2") (pinfunction "2_2") (pintype "passive"))
      (node (ref "U7") (pin "3") (pinfunction "IN_P_3") (pintype "input"))
    )
    (net (code "73") (name "VBAT") (class "Default")
      (node (ref "C5") (pin "1") (pinfunction "1_1") (pintype "passive"))
      (node (ref "Q3") (pin "3") (pinfunction "D_3") (pintype "passive"))
      (node (ref "R4") (pin "1") (pinfunction "1_1") (pintype "passive"))
      (node (ref "U3") (pin "3") (pinfunction "VBAT_3") (pintype "power_in"))
      (node (ref "X2") (pin "2") (pinfunction "2_2") (pintype "passive"))
    )
    (net (code "74") (name "VBUS") (class "Default")
      (node (ref "CHG") (pin "A") (pinfunction "A_A") (pintype "passive"))
      (node (ref "D5") (pin "A") (pinfunction "A_A") (pintype "passive"))
      (node (ref "Q3") (pin "1") (pinfunction "G_1") (pintype "passive"))
      (node (ref "R12") (pin "1") (pinfunction "1_1") (pintype "passive"))
      (node (ref "U3") (pin "4") (pinfunction "VDD_4") (pintype "power_in"))
      (node (ref "X3") (pin "VBUS") (pinfunction "VBUS_VBUS") (pintype "power_in"))
    )
    (net (code "75") (name "VCCA") (class "Default")
      (node (ref "C11") (pin "1") (pinfunction "1_1") (pintype "passive"))
      (node (ref "L1") (pin "2") (pinfunction "2_2") (pintype "passive"))
      (node (ref "R10") (pin "1") (pinfunction "1_1") (pintype "passive"))
      (node (ref "R8") (pin "1") (pinfunction "1_1") (pintype "passive"))
      (node (ref "U4") (pin "4") (pinfunction "P$V+_4") (pintype "bidirectional"))
    )
    (net (code "76") (name "VCC_2") (class "Default")
      (node (ref "C16") (pin "1") (pinfunction "1_1") (pintype "passive"))
      (node (ref "C17") (pin "1") (pinfunction "1_1") (pintype "passive"))
      (node (ref "C18") (pin "1") (pinfunction "1_1") (pintype "passive"))
      (node (ref "C21") (pin "1") (pinfunction "1_1") (pintype "passive"))
      (node (ref "C26") (pin "1") (pinfunction "1_1") (pintype "passive"))
      (node (ref "R20") (pin "1") (pinfunction "1_1") (pintype "passive"))
      (node (ref "R25") (pin "1") (pinfunction "1_1") (pintype "passive"))
      (node (ref "U$45") (pin "V_CC") (pinfunction "VCC_V_CC") (pintype "bidirectional"))
      (node (ref "U$51") (pin "V_CC") (pinfunction "VCC_V_CC") (pintype "bidirectional"))
      (node (ref "U5") (pin "5") (pinfunction "OUT_5") (pintype "power_in"))
      (node (ref "U6") (pin "6") (pinfunction "VDD_6") (pintype "power_in"))
      (node (ref "U7") (pin "6") (pinfunction "VDD_6") (pintype "power_in"))
    )
    (net (code "77") (name "unconnected-(U$51-CO-PadCL_OUT)") (class "Default")
      (node (ref "U$51") (pin "CL_OUT") (pinfunction "CO_CL_OUT") (pintype "bidirectional"))
    )
    (net (code "78") (name "unconnected-(U$51-DO-PadD_OUT)") (class "Default")
      (node (ref "U$51") (pin "D_OUT") (pinfunction "DO_D_OUT") (pintype "bidirectional"))
    )
    (net (code "79") (name "unconnected-(U1-P0.23-Pad41)") (class "Default")
      (node (ref "U1") (pin "41") (pinfunction "P0.23_41") (pintype "bidirectional"))
    )
    (net (code "80") (name "unconnected-(U1-P0.24-Pad40)") (class "Default")
      (node (ref "U1") (pin "40") (pinfunction "P0.24_40") (pintype "bidirectional"))
    )
    (net (code "81") (name "unconnected-(U2-P4-Pad4)") (class "Default")
      (node (ref "U2") (pin "4") (pinfunction "P4_4") (pintype "bidirectional"))
    )
    (net (code "82") (name "unconnected-(U4D-+IN-Pad12)") (class "Default")
      (node (ref "U4") (pin "12") (pinfunction "+IN_12") (pintype "input"))
    )
    (net (code "83") (name "unconnected-(U4D--IN-Pad13)") (class "Default")
      (node (ref "U4") (pin "13") (pinfunction "-IN_13") (pintype "input"))
    )
    (net (code "84") (name "unconnected-(U4D-OUT-Pad14)") (class "Default")
      (node (ref "U4") (pin "14") (pinfunction "OUT_14") (pintype "output"))
    )
    (net (code "85") (name "unconnected-(U5-P4-Pad4)") (class "Default")
      (node (ref "U5") (pin "4") (pinfunction "P4_4") (pintype "bidirectional"))
    )
    (net (code "86") (name "unconnected-(U6-NC-Pad2)") (class "Default")
      (node (ref "U6") (pin "2") (pinfunction "NC_2") (pintype "no_connect"))
    )
    (net (code "87") (name "unconnected-(U7-NC-Pad2)") (class "Default")
      (node (ref "U7") (pin "2") (pinfunction "NC_2") (pintype "no_connect"))
    )
    (net (code "88") (name "unconnected-(X3-PadID)") (class "Default")
      (node (ref "X3") (pin "ID") (pinfunction "ID_ID") (pintype "bidirectional"))
    )
  )
)
